# 3_3V_DIST.net
KiCad netlist of a schematic drawn in Altium Designer
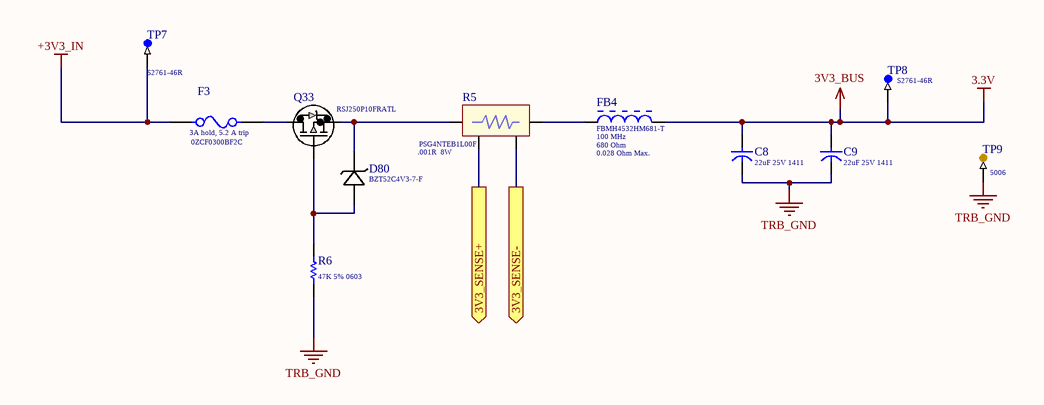
[diagram p0: 3_3V_DIST.SchDoc]

(export (version "E")
  (design (tool "Eeschema 10.0.6"))
  (components
    (comp (ref "C8")
      (value "Cap_Kemet_T521B226M025ATE100_22uF")
      (footprint "Cap_Kemet_T521B226M025ATE100_22uF")
      (description "Tantalum Capacitors - Polymer SMD 25V 22uF 1311 20% ESR=100mOhms")
      (fields (field (name "CAPACITANCE") "22uF 25V 1411"))
      (libsource (lib "Cap_Kemet_T521B226M025ATE100_22uF") (part "Cap_Kemet_T521B226M025ATE100_22uF"))
    )
    (comp (ref "C9")
      (value "Cap_Kemet_T521B226M025ATE100_22uF")
      (footprint "Cap_Kemet_T521B226M025ATE100_22uF")
      (description "Tantalum Capacitors - Polymer SMD 25V 22uF 1311 20% ESR=100mOhms")
      (fields (field (name "CAPACITANCE") "22uF 25V 1411"))
      (libsource (lib "Cap_Kemet_T521B226M025ATE100_22uF") (part "Cap_Kemet_T521B226M025ATE100_22uF"))
    )
    (comp (ref "D80")
      (value "BZT52C4V3-7-F")
      (footprint "SOD123")
      (description "Zener Diodes 500mW 4.3V Zener AEC-Q101 Qualified")
      (fields (field (name "SERIES") "BZT52C4V3-7-F"))
      (libsource (lib "4v3_zener_BZT52C4V3-7-F") (part "BZT52C4V3-7-F"))
    )
    (comp (ref "F3")
      (value "3A hold, 5.2 A trip")
      (footprint "Bel_0ZCF_MFG")
      (description "Resettable Fuses - PPTC 3A 24V PPTC 2920 SMD")
      (fields (field (name "SERIES") "0ZCF0300BF2C"))
      (libsource (lib "Fuse_Bel_0ZCF0300BF2C_3A_hold") (part "0ZCF0300BF2C"))
    )
    (comp (ref "FB4")
      (value "FBMH4532HM681-T")
      (footprint "TAYO-FBMH4532-2_V")
      (fields
        (field (name "PARTNUMBER") "FBMH4532HM681-T")
        (field (name "MANUFACTURER") "Taiyo Yuden")
        (field (name "MEASURING FREQUENCY") "100 MHz")
        (field (name "NOMINAL IMPEDANCE") "680 Ohm")
        (field (name "DC RESISTANCE") "0.028 Ohm Max.")
      )
      (libsource (lib "Taiyo_Yuden_FBMH4532HM681") (part "FBMH4532HM681-T"))
    )
    (comp (ref "Q33")
      (value "Mos_ROHM_RSJ250P10FRATL_25A")
      (footprint "Mos_ROHM_RSJ250P10FRATL_25A")
      (description "MOSFET Pch -100V Vds -25A 0.05Rds(on) 60Qg")
      (fields (field (name "SERIES") "RSJ250P10FRATL"))
      (libsource (lib "Mos_ROHM_RSJ250P10FRATL_25A") (part "Mos_ROHM_RSJ250P10FRATL_25A"))
    )
    (comp (ref "R5")
      (value "SRes_KOA_PSG4NTEB1L00F_1mOhm")
      (footprint "SRes_KOA_PSG4NTEB1L00F_1mOhm")
      (description "Current Sense Resistors - SMD 1mOhm 8W 1% 50ppm AEC-Q200 Power Shunt")
      (fields
        (field (name "RESISTANCE") ".001R")
        (field (name "SERIES") "PSG4NTEB1L00F")
        (field (name "PARAMETER 1") "8W")
      )
      (libsource (lib "SRes_KOA_PSG4NTEB1L00F_1mOhm") (part "SRes_KOA_PSG4NTEB1L00F_1mOhm"))
    )
    (comp (ref "R6")
      (value "47K 5% 0603")
      (footprint "RESC0603(1608)_L")
      (description "47K 0.1W 5% 0603 (1608 Metric)  SMD")
      (fields (field (name "TOLERANCE") "5 %") (field (name "POWER") "0.1 W"))
      (libsource (lib "Altium Content Vault") (part "RES"))
    )
    (comp (ref "TP7")
      (value "TP_Harwin_S2761_46R")
      (footprint "TP_Harwin_S2761_46R")
      (description "Circuit Board Hardware - PCB SMT Mini Test Terminal, Reel")
      (fields (field (name "SERIES") "S2761-46R"))
      (libsource (lib "TP_Harwin_S2761_46R") (part "TP_Harwin_S2761_46R"))
    )
    (comp (ref "TP8")
      (value "TP_Harwin_S2761_46R")
      (footprint "TP_Harwin_S2761_46R")
      (description "Circuit Board Hardware - PCB SMT Mini Test Terminal, Reel")
      (fields (field (name "SERIES") "S2761-46R"))
      (libsource (lib "TP_Harwin_S2761_46R") (part "TP_Harwin_S2761_46R"))
    )
    (comp (ref "TP9")
      (value "TP_Keystone_Electronics_5006")
      (footprint "TP_Keystone_Electronics_5006")
      (description "Circuit Board Hardware - PCB TEST POINT BLK .063")
      (fields (field (name "SERIES") "5006"))
      (libsource (lib "TP_Keystone_Electronics_5006") (part "TP_Keystone_Electronics_5006"))
    )
  )
  (nets
    (net (code "1") (name "+3V3_IN") (class "Default")
      (node (ref "F3") (pin "1") (pinfunction "1_1") (pintype "passive"))
      (node (ref "TP7") (pin "1") (pinfunction "1_1") (pintype "input"))
    )
    (net (code "2") (name "/3V3_SENSE+") (class "Default")
      (node (ref "R5") (pin "4") (pinfunction "4_4") (pintype "passive"))
    )
    (net (code "3") (name "/3V3_SENSE-") (class "Default")
      (node (ref "R5") (pin "3") (pinfunction "3_3") (pintype "passive"))
    )
    (net (code "4") (name "3.3V") (class "Default")
      (node (ref "C8") (pin "1") (pinfunction "1_1") (pintype "passive"))
      (node (ref "C9") (pin "1") (pinfunction "1_1") (pintype "passive"))
      (node (ref "FB4") (pin "2") (pinfunction "2_2") (pintype "passive"))
      (node (ref "TP8") (pin "1") (pinfunction "1_1") (pintype "input"))
    )
    (net (code "5") (name "Net-(FB4-Pad1)") (class "Default")
      (node (ref "FB4") (pin "1") (pinfunction "1_1") (pintype "passive"))
      (node (ref "R5") (pin "2") (pinfunction "2_2") (pintype "passive"))
    )
    (net (code "6") (name "Net-(Q33-D)") (class "Default")
      (node (ref "F3") (pin "2") (pinfunction "2_2") (pintype "passive"))
      (node (ref "Q33") (pin "2") (pinfunction "D_2") (pintype "passive"))
    )
    (net (code "7") (name "Net-(Q33-G)") (class "Default")
      (node (ref "D80") (pin "2") (pinfunction "2_2") (pintype "passive"))
      (node (ref "Q33") (pin "1") (pinfunction "G_1") (pintype "passive"))
      (node (ref "R6") (pin "2") (pinfunction "2_2") (pintype "passive"))
    )
    (net (code "8") (name "Net-(Q33-S)") (class "Default")
      (node (ref "D80") (pin "1") (pinfunction "1_1") (pintype "passive"))
      (node (ref "Q33") (pin "3") (pinfunction "S_3") (pintype "passive"))
      (node (ref "R5") (pin "1") (pinfunction "1_1") (pintype "passive"))
    )
    (net (code "9") (name "TRB_GND") (class "Default")
      (node (ref "C8") (pin "2") (pinfunction "2_2") (pintype "passive"))
      (node (ref "C9") (pin "2") (pinfunction "2_2") (pintype "passive"))
      (node (ref "R6") (pin "1") (pinfunction "1_1") (pintype "passive"))
      (node (ref "TP9") (pin "1") (pinfunction "1_1") (pintype "input"))
    )
  )
)
